# VidRayCurrentMonitor.net
KiCad netlist of a schematic drawn in Altium Designer
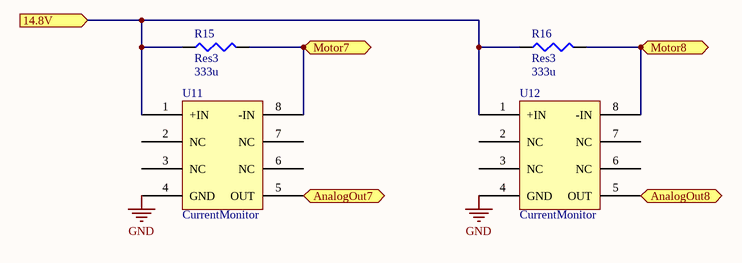
[diagram p0: VidRayCurrentMonitor.SchDoc]

(export (version "E")
  (design (tool "Eeschema 10.0.6"))
  (components
    (comp (ref "R15")
      (value "Res3")
      (footprint "Resistor03mOhm")
      (description "Resistor")
      (fields (field (name "ALTIUM_VALUE") "333u") (field (name "PUBLISHER") "Altium Limited"))
      (libsource (lib "Miscellaneous Devices") (part "Res3"))
    )
    (comp (ref "R16")
      (value "Res3")
      (footprint "Resistor03mOhm")
      (description "Resistor")
      (fields (field (name "ALTIUM_VALUE") "333u") (field (name "PUBLISHER") "Altium Limited"))
      (libsource (lib "Miscellaneous Devices") (part "Res3"))
    )
    (comp (ref "U11")
      (value "CurrentMonitor")
      (footprint "AD8217")
      (libsource (lib "AD8217") (part "AD8217"))
    )
    (comp (ref "U12")
      (value "CurrentMonitor")
      (footprint "AD8217")
      (libsource (lib "AD8217") (part "AD8217"))
    )
  )
  (nets
    (net (code "1") (name "/14.8V") (class "Default")
      (node (ref "R15") (pin "1") (pinfunction "1_1") (pintype "passive"))
      (node (ref "R16") (pin "1") (pinfunction "1_1") (pintype "passive"))
      (node (ref "U11") (pin "1") (pinfunction "+IN_1") (pintype "passive"))
      (node (ref "U12") (pin "1") (pinfunction "+IN_1") (pintype "passive"))
    )
    (net (code "2") (name "/AnalogOut7") (class "Default")
      (node (ref "U11") (pin "5") (pinfunction "OUT_5") (pintype "passive"))
    )
    (net (code "3") (name "/AnalogOut8") (class "Default")
      (node (ref "U12") (pin "5") (pinfunction "OUT_5") (pintype "passive"))
    )
    (net (code "4") (name "/Motor7") (class "Default")
      (node (ref "R15") (pin "2") (pinfunction "2_2") (pintype "passive"))
      (node (ref "U11") (pin "8") (pinfunction "-IN_8") (pintype "passive"))
    )
    (net (code "5") (name "/Motor8") (class "Default")
      (node (ref "R16") (pin "2") (pinfunction "2_2") (pintype "passive"))
      (node (ref "U12") (pin "8") (pinfunction "-IN_8") (pintype "passive"))
    )
    (net (code "6") (name "GND") (class "Default")
      (node (ref "U11") (pin "4") (pinfunction "GND_4") (pintype "passive"))
      (node (ref "U12") (pin "4") (pinfunction "GND_4") (pintype "passive"))
    )
    (net (code "7") (name "unconnected-(U11-NC-Pad2)") (class "Default")
      (node (ref "U11") (pin "2") (pinfunction "NC_2") (pintype "passive"))
    )
    (net (code "8") (name "unconnected-(U11-NC-Pad3)") (class "Default")
      (node (ref "U11") (pin "3") (pinfunction "NC_3") (pintype "passive"))
    )
    (net (code "9") (name "unconnected-(U11-NC-Pad6)") (class "Default")
      (node (ref "U11") (pin "6") (pinfunction "NC_6") (pintype "passive"))
    )
    (net (code "10") (name "unconnected-(U11-NC-Pad7)") (class "Default")
      (node (ref "U11") (pin "7") (pinfunction "NC_7") (pintype "passive"))
    )
    (net (code "11") (name "unconnected-(U12-NC-Pad2)") (class "Default")
      (node (ref "U12") (pin "2") (pinfunction "NC_2") (pintype "passive"))
    )
    (net (code "12") (name "unconnected-(U12-NC-Pad3)") (class "Default")
      (node (ref "U12") (pin "3") (pinfunction "NC_3") (pintype "passive"))
    )
    (net (code "13") (name "unconnected-(U12-NC-Pad6)") (class "Default")
      (node (ref "U12") (pin "6") (pinfunction "NC_6") (pintype "passive"))
    )
    (net (code "14") (name "unconnected-(U12-NC-Pad7)") (class "Default")
      (node (ref "U12") (pin "7") (pinfunction "NC_7") (pintype "passive"))
    )
  )
)
